# minimumSystem_1.net
KiCad netlist of a schematic drawn in EAGLE
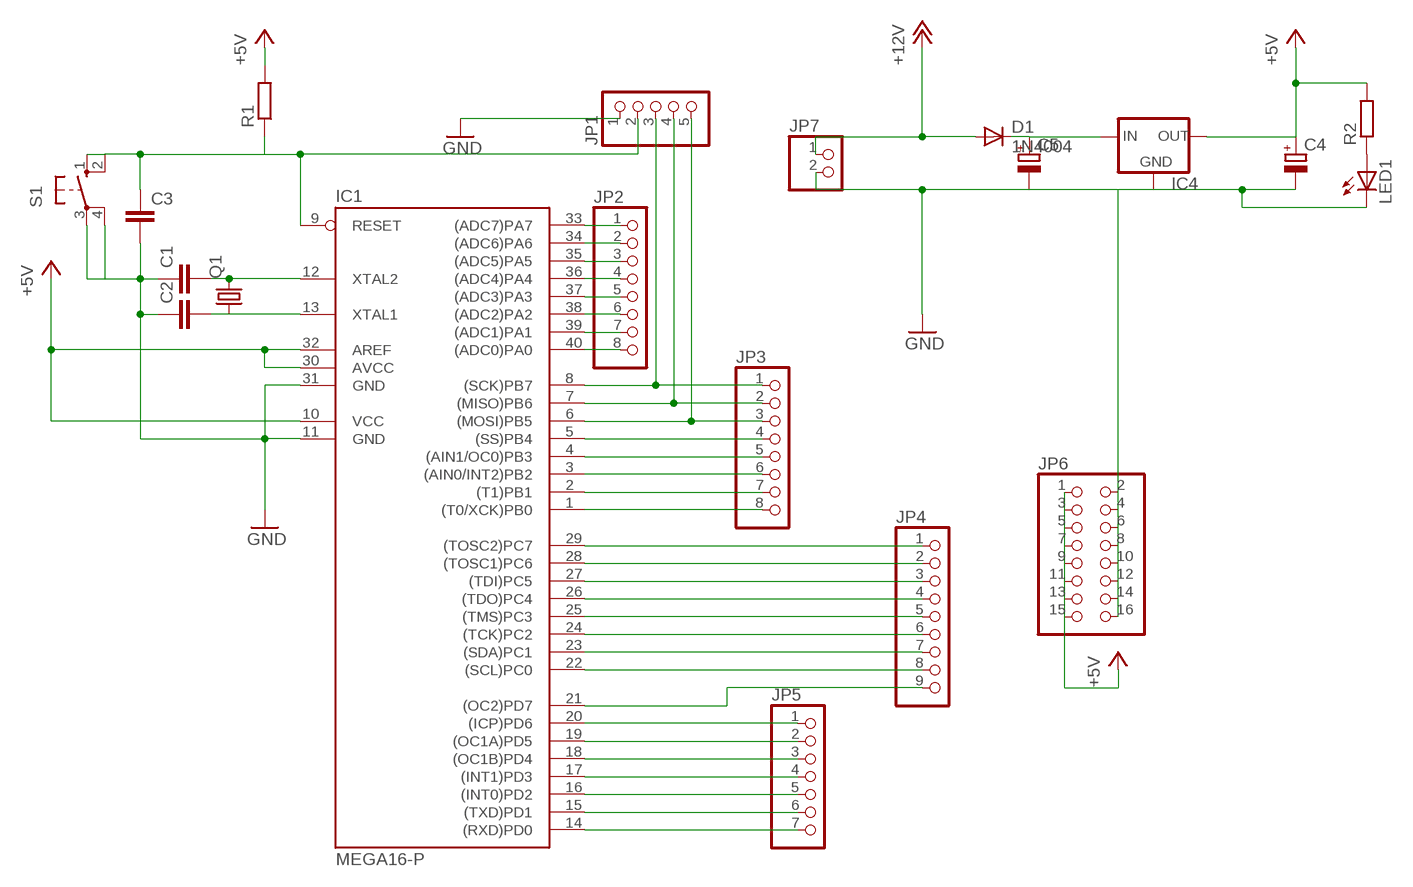
[diagram p0: schematic, sheet 1]

(export (version "E")
  (design (tool "Eeschema 10.0.6"))
  (components
    (comp (ref "C1")
      (value "C-EU025-024X044")
      (footprint "eagle-import:C025-024X044")
      (libsource (lib "eagle-import") (part "C-EU025-024X044"))
    )
    (comp (ref "C2")
      (value "C-EU025-024X044")
      (footprint "eagle-import:C025-024X044")
      (libsource (lib "eagle-import") (part "C-EU025-024X044"))
    )
    (comp (ref "C3")
      (value "C-EU050-025X075")
      (footprint "eagle-import:C050-025X075")
      (libsource (lib "eagle-import") (part "resistor_C-EU050-025X075"))
    )
    (comp (ref "C4")
      (value "CPOL-EUE2.5-5")
      (footprint "eagle-import:E2,5-5")
      (libsource (lib "eagle-import") (part "CPOL-EUE2.5-5"))
    )
    (comp (ref "C5")
      (value "CPOL-EUE2.5-5")
      (footprint "eagle-import:E2,5-5")
      (libsource (lib "eagle-import") (part "CPOL-EUE2.5-5"))
    )
    (comp (ref "D1")
      (value "1N4004")
      (footprint "eagle-import:DO41-10")
      (libsource (lib "eagle-import") (part "1N4004"))
    )
    (comp (ref "IC1")
      (value "MEGA16-P")
      (footprint "eagle-import:DIL40")
      (fields (field (name "MPN") "ATMEGA16-16PU"))
      (libsource (lib "eagle-import") (part "MEGA16-P"))
    )
    (comp (ref "IC4")
      (value "78XXS")
      (footprint "eagle-import:78XXS")
      (libsource (lib "eagle-import") (part "78XXS"))
    )
    (comp (ref "JP1")
      (value "PINHD-1X5")
      (footprint "eagle-import:1X05")
      (libsource (lib "eagle-import") (part "PINHD-1X5"))
    )
    (comp (ref "JP2")
      (value "PINHD-1X8")
      (footprint "eagle-import:1X08")
      (libsource (lib "eagle-import") (part "PINHD-1X8"))
    )
    (comp (ref "JP3")
      (value "PINHD-1X8")
      (footprint "eagle-import:1X08")
      (libsource (lib "eagle-import") (part "PINHD-1X8"))
    )
    (comp (ref "JP4")
      (value "PINHD-1X9")
      (footprint "eagle-import:1X09")
      (libsource (lib "eagle-import") (part "PINHD-1X9"))
    )
    (comp (ref "JP5")
      (value "PINHD-1X7")
      (footprint "eagle-import:1X07")
      (libsource (lib "eagle-import") (part "PINHD-1X7"))
    )
    (comp (ref "JP6")
      (value "PINHD-2X8")
      (footprint "eagle-import:2X08")
      (libsource (lib "eagle-import") (part "PINHD-2X8"))
    )
    (comp (ref "JP7")
      (value "PINHD-1X2")
      (footprint "eagle-import:1X02")
      (libsource (lib "eagle-import") (part "PINHD-1X2"))
    )
    (comp (ref "LED1")
      (value "LED5MM")
      (footprint "eagle-import:LED5MM")
      (libsource (lib "eagle-import") (part "LED5MM"))
    )
    (comp (ref "Q1")
      (value "CRYSTALHC49U-V")
      (footprint "eagle-import:HC49U-V")
      (libsource (lib "eagle-import") (part "CRYSTALHC49U-V"))
    )
    (comp (ref "R1")
      (value "R-EU_0204/7")
      (footprint "eagle-import:0204_7")
      (libsource (lib "eagle-import") (part "R-EU_0204/7"))
    )
    (comp (ref "R2")
      (value "R-EU_0204/7")
      (footprint "eagle-import:0204_7")
      (libsource (lib "eagle-import") (part "R-EU_0204/7"))
    )
    (comp (ref "S1")
      (value "10-XX")
      (footprint "eagle-import:B3F-10XX")
      (fields (field (name "MPN") "B3F-1000"))
      (libsource (lib "eagle-import") (part "10-XX"))
    )
  )
  (nets
    (net (code "1") (name "+5V") (class "Default")
      (node (ref "C4") (pin "+") (pinfunction "+_+") (pintype "passive"))
      (node (ref "IC1") (pin "10") (pinfunction "VCC_10") (pintype "power_in"))
      (node (ref "IC1") (pin "30") (pinfunction "AVCC_30") (pintype "power_in"))
      (node (ref "IC1") (pin "32") (pinfunction "AREF_32") (pintype "passive"))
      (node (ref "IC4") (pin "OUT") (pinfunction "OUT_OUT") (pintype "passive"))
      (node (ref "JP6") (pin "1") (pinfunction "1_1") (pintype "passive"))
      (node (ref "JP6") (pin "11") (pinfunction "11_11") (pintype "passive"))
      (node (ref "JP6") (pin "13") (pinfunction "13_13") (pintype "passive"))
      (node (ref "JP6") (pin "15") (pinfunction "15_15") (pintype "passive"))
      (node (ref "JP6") (pin "3") (pinfunction "3_3") (pintype "passive"))
      (node (ref "JP6") (pin "5") (pinfunction "5_5") (pintype "passive"))
      (node (ref "JP6") (pin "7") (pinfunction "7_7") (pintype "passive"))
      (node (ref "JP6") (pin "9") (pinfunction "9_9") (pintype "passive"))
      (node (ref "R1") (pin "2") (pinfunction "2_2") (pintype "passive"))
      (node (ref "R2") (pin "2") (pinfunction "2_2") (pintype "passive"))
    )
    (net (code "2") (name "+12V") (class "Default")
      (node (ref "D1") (pin "A") (pinfunction "A_A") (pintype "passive"))
      (node (ref "JP7") (pin "1") (pinfunction "1_1") (pintype "passive"))
    )
    (net (code "3") (name "GND") (class "Default")
      (node (ref "C1") (pin "1") (pinfunction "1_1") (pintype "passive"))
      (node (ref "C2") (pin "1") (pinfunction "1_1") (pintype "passive"))
      (node (ref "C3") (pin "2") (pinfunction "2_2") (pintype "passive"))
      (node (ref "C4") (pin "-") (pinfunction "-_-") (pintype "passive"))
      (node (ref "C5") (pin "-") (pinfunction "-_-") (pintype "passive"))
      (node (ref "IC1") (pin "11") (pinfunction "GND_11") (pintype "power_in"))
      (node (ref "IC1") (pin "31") (pinfunction "GND_31") (pintype "power_in"))
      (node (ref "IC4") (pin "GND") (pinfunction "GND_GND") (pintype "input"))
      (node (ref "JP1") (pin "1") (pinfunction "1_1") (pintype "passive"))
      (node (ref "JP6") (pin "10") (pinfunction "10_10") (pintype "passive"))
      (node (ref "JP6") (pin "12") (pinfunction "12_12") (pintype "passive"))
      (node (ref "JP6") (pin "14") (pinfunction "14_14") (pintype "passive"))
      (node (ref "JP6") (pin "16") (pinfunction "16_16") (pintype "passive"))
      (node (ref "JP6") (pin "2") (pinfunction "2_2") (pintype "passive"))
      (node (ref "JP6") (pin "4") (pinfunction "4_4") (pintype "passive"))
      (node (ref "JP6") (pin "6") (pinfunction "6_6") (pintype "passive"))
      (node (ref "JP6") (pin "8") (pinfunction "8_8") (pintype "passive"))
      (node (ref "JP7") (pin "2") (pinfunction "2_2") (pintype "passive"))
      (node (ref "LED1") (pin "K") (pinfunction "C_K") (pintype "passive"))
      (node (ref "S1") (pin "3") (pinfunction "P_3") (pintype "passive"))
      (node (ref "S1") (pin "4") (pinfunction "P1_4") (pintype "passive"))
    )
    (net (code "4") (name "Net-(C5-Pad+)") (class "Default")
      (node (ref "C5") (pin "+") (pinfunction "+_+") (pintype "passive"))
      (node (ref "D1") (pin "C") (pinfunction "C_C") (pintype "passive"))
      (node (ref "IC4") (pin "IN") (pinfunction "IN_IN") (pintype "input"))
    )
    (net (code "5") (name "Net-(IC1-(ADC0)PA0)") (class "Default")
      (node (ref "IC1") (pin "40") (pinfunction "(ADC0)PA0_40") (pintype "bidirectional"))
      (node (ref "JP2") (pin "8") (pinfunction "8_8") (pintype "passive"))
    )
    (net (code "6") (name "Net-(IC1-(ADC1)PA1)") (class "Default")
      (node (ref "IC1") (pin "39") (pinfunction "(ADC1)PA1_39") (pintype "bidirectional"))
      (node (ref "JP2") (pin "7") (pinfunction "7_7") (pintype "passive"))
    )
    (net (code "7") (name "Net-(IC1-(ADC2)PA2)") (class "Default")
      (node (ref "IC1") (pin "38") (pinfunction "(ADC2)PA2_38") (pintype "bidirectional"))
      (node (ref "JP2") (pin "6") (pinfunction "6_6") (pintype "passive"))
    )
    (net (code "8") (name "Net-(IC1-(ADC3)PA3)") (class "Default")
      (node (ref "IC1") (pin "37") (pinfunction "(ADC3)PA3_37") (pintype "bidirectional"))
      (node (ref "JP2") (pin "5") (pinfunction "5_5") (pintype "passive"))
    )
    (net (code "9") (name "Net-(IC1-(ADC4)PA4)") (class "Default")
      (node (ref "IC1") (pin "36") (pinfunction "(ADC4)PA4_36") (pintype "bidirectional"))
      (node (ref "JP2") (pin "4") (pinfunction "4_4") (pintype "passive"))
    )
    (net (code "10") (name "Net-(IC1-(ADC5)PA5)") (class "Default")
      (node (ref "IC1") (pin "35") (pinfunction "(ADC5)PA5_35") (pintype "bidirectional"))
      (node (ref "JP2") (pin "3") (pinfunction "3_3") (pintype "passive"))
    )
    (net (code "11") (name "Net-(IC1-(ADC6)PA6)") (class "Default")
      (node (ref "IC1") (pin "34") (pinfunction "(ADC6)PA6_34") (pintype "bidirectional"))
      (node (ref "JP2") (pin "2") (pinfunction "2_2") (pintype "passive"))
    )
    (net (code "12") (name "Net-(IC1-(ADC7)PA7)") (class "Default")
      (node (ref "IC1") (pin "33") (pinfunction "(ADC7)PA7_33") (pintype "bidirectional"))
      (node (ref "JP2") (pin "1") (pinfunction "1_1") (pintype "passive"))
    )
    (net (code "13") (name "Net-(IC1-(AIN0{slash}INT2)PB2)") (class "Default")
      (node (ref "IC1") (pin "3") (pinfunction "(AIN0/INT2)PB2_3") (pintype "bidirectional"))
      (node (ref "JP3") (pin "6") (pinfunction "6_6") (pintype "passive"))
    )
    (net (code "14") (name "Net-(IC1-(AIN1{slash}OC0)PB3)") (class "Default")
      (node (ref "IC1") (pin "4") (pinfunction "(AIN1/OC0)PB3_4") (pintype "bidirectional"))
      (node (ref "JP3") (pin "5") (pinfunction "5_5") (pintype "passive"))
    )
    (net (code "15") (name "Net-(IC1-(ICP)PD6)") (class "Default")
      (node (ref "IC1") (pin "20") (pinfunction "(ICP)PD6_20") (pintype "bidirectional"))
      (node (ref "JP5") (pin "1") (pinfunction "1_1") (pintype "passive"))
    )
    (net (code "16") (name "Net-(IC1-(INT0)PD2)") (class "Default")
      (node (ref "IC1") (pin "16") (pinfunction "(INT0)PD2_16") (pintype "bidirectional"))
      (node (ref "JP5") (pin "5") (pinfunction "5_5") (pintype "passive"))
    )
    (net (code "17") (name "Net-(IC1-(INT1)PD3)") (class "Default")
      (node (ref "IC1") (pin "17") (pinfunction "(INT1)PD3_17") (pintype "bidirectional"))
      (node (ref "JP5") (pin "4") (pinfunction "4_4") (pintype "passive"))
    )
    (net (code "18") (name "Net-(IC1-(MISO)PB6)") (class "Default")
      (node (ref "IC1") (pin "7") (pinfunction "(MISO)PB6_7") (pintype "bidirectional"))
      (node (ref "JP1") (pin "4") (pinfunction "4_4") (pintype "passive"))
      (node (ref "JP3") (pin "2") (pinfunction "2_2") (pintype "passive"))
    )
    (net (code "19") (name "Net-(IC1-(MOSI)PB5)") (class "Default")
      (node (ref "IC1") (pin "6") (pinfunction "(MOSI)PB5_6") (pintype "bidirectional"))
      (node (ref "JP1") (pin "5") (pinfunction "5_5") (pintype "passive"))
      (node (ref "JP3") (pin "3") (pinfunction "3_3") (pintype "passive"))
    )
    (net (code "20") (name "Net-(IC1-(OC1A)PD5)") (class "Default")
      (node (ref "IC1") (pin "19") (pinfunction "(OC1A)PD5_19") (pintype "bidirectional"))
      (node (ref "JP5") (pin "2") (pinfunction "2_2") (pintype "passive"))
    )
    (net (code "21") (name "Net-(IC1-(OC1B)PD4)") (class "Default")
      (node (ref "IC1") (pin "18") (pinfunction "(OC1B)PD4_18") (pintype "bidirectional"))
      (node (ref "JP5") (pin "3") (pinfunction "3_3") (pintype "passive"))
    )
    (net (code "22") (name "Net-(IC1-(OC2)PD7)") (class "Default")
      (node (ref "IC1") (pin "21") (pinfunction "(OC2)PD7_21") (pintype "bidirectional"))
      (node (ref "JP4") (pin "9") (pinfunction "9_9") (pintype "passive"))
    )
    (net (code "23") (name "Net-(IC1-(RXD)PD0)") (class "Default")
      (node (ref "IC1") (pin "14") (pinfunction "(RXD)PD0_14") (pintype "bidirectional"))
      (node (ref "JP5") (pin "7") (pinfunction "7_7") (pintype "passive"))
    )
    (net (code "24") (name "Net-(IC1-(SCK)PB7)") (class "Default")
      (node (ref "IC1") (pin "8") (pinfunction "(SCK)PB7_8") (pintype "bidirectional"))
      (node (ref "JP1") (pin "3") (pinfunction "3_3") (pintype "passive"))
      (node (ref "JP3") (pin "1") (pinfunction "1_1") (pintype "passive"))
    )
    (net (code "25") (name "Net-(IC1-(SCL)PC0)") (class "Default")
      (node (ref "IC1") (pin "22") (pinfunction "(SCL)PC0_22") (pintype "bidirectional"))
      (node (ref "JP4") (pin "8") (pinfunction "8_8") (pintype "passive"))
    )
    (net (code "26") (name "Net-(IC1-(SDA)PC1)") (class "Default")
      (node (ref "IC1") (pin "23") (pinfunction "(SDA)PC1_23") (pintype "bidirectional"))
      (node (ref "JP4") (pin "7") (pinfunction "7_7") (pintype "passive"))
    )
    (net (code "27") (name "Net-(IC1-(SS)PB4)") (class "Default")
      (node (ref "IC1") (pin "5") (pinfunction "(SS)PB4_5") (pintype "bidirectional"))
      (node (ref "JP3") (pin "4") (pinfunction "4_4") (pintype "passive"))
    )
    (net (code "28") (name "Net-(IC1-(T0{slash}XCK)PB0)") (class "Default")
      (node (ref "IC1") (pin "1") (pinfunction "(T0/XCK)PB0_1") (pintype "bidirectional"))
      (node (ref "JP3") (pin "8") (pinfunction "8_8") (pintype "passive"))
    )
    (net (code "29") (name "Net-(IC1-(T1)PB1)") (class "Default")
      (node (ref "IC1") (pin "2") (pinfunction "(T1)PB1_2") (pintype "bidirectional"))
      (node (ref "JP3") (pin "7") (pinfunction "7_7") (pintype "passive"))
    )
    (net (code "30") (name "Net-(IC1-(TCK)PC2)") (class "Default")
      (node (ref "IC1") (pin "24") (pinfunction "(TCK)PC2_24") (pintype "bidirectional"))
      (node (ref "JP4") (pin "6") (pinfunction "6_6") (pintype "passive"))
    )
    (net (code "31") (name "Net-(IC1-(TDI)PC5)") (class "Default")
      (node (ref "IC1") (pin "27") (pinfunction "(TDI)PC5_27") (pintype "bidirectional"))
      (node (ref "JP4") (pin "3") (pinfunction "3_3") (pintype "passive"))
    )
    (net (code "32") (name "Net-(IC1-(TDO)PC4)") (class "Default")
      (node (ref "IC1") (pin "26") (pinfunction "(TDO)PC4_26") (pintype "bidirectional"))
      (node (ref "JP4") (pin "4") (pinfunction "4_4") (pintype "passive"))
    )
    (net (code "33") (name "Net-(IC1-(TMS)PC3)") (class "Default")
      (node (ref "IC1") (pin "25") (pinfunction "(TMS)PC3_25") (pintype "bidirectional"))
      (node (ref "JP4") (pin "5") (pinfunction "5_5") (pintype "passive"))
    )
    (net (code "34") (name "Net-(IC1-(TOSC1)PC6)") (class "Default")
      (node (ref "IC1") (pin "28") (pinfunction "(TOSC1)PC6_28") (pintype "bidirectional"))
      (node (ref "JP4") (pin "2") (pinfunction "2_2") (pintype "passive"))
    )
    (net (code "35") (name "Net-(IC1-(TOSC2)PC7)") (class "Default")
      (node (ref "IC1") (pin "29") (pinfunction "(TOSC2)PC7_29") (pintype "bidirectional"))
      (node (ref "JP4") (pin "1") (pinfunction "1_1") (pintype "passive"))
    )
    (net (code "36") (name "Net-(IC1-(TXD)PD1)") (class "Default")
      (node (ref "IC1") (pin "15") (pinfunction "(TXD)PD1_15") (pintype "bidirectional"))
      (node (ref "JP5") (pin "6") (pinfunction "6_6") (pintype "passive"))
    )
    (net (code "37") (name "Net-(IC1-RESET)") (class "Default")
      (node (ref "C3") (pin "1") (pinfunction "1_1") (pintype "passive"))
      (node (ref "IC1") (pin "9") (pinfunction "RESET_9") (pintype "input"))
      (node (ref "JP1") (pin "2") (pinfunction "2_2") (pintype "passive"))
      (node (ref "S1") (pin "1") (pinfunction "S_1") (pintype "passive"))
      (node (ref "S1") (pin "2") (pinfunction "S1_2") (pintype "passive"))
    )
    (net (code "38") (name "Net-(IC1-XTAL1)") (class "Default")
      (node (ref "C2") (pin "2") (pinfunction "2_2") (pintype "passive"))
      (node (ref "IC1") (pin "13") (pinfunction "XTAL1_13") (pintype "bidirectional"))
      (node (ref "Q1") (pin "1") (pinfunction "1_1") (pintype "passive"))
    )
    (net (code "39") (name "Net-(IC1-XTAL2)") (class "Default")
      (node (ref "C1") (pin "2") (pinfunction "2_2") (pintype "passive"))
      (node (ref "IC1") (pin "12") (pinfunction "XTAL2_12") (pintype "bidirectional"))
      (node (ref "Q1") (pin "2") (pinfunction "2_2") (pintype "passive"))
    )
    (net (code "40") (name "Net-(LED1-PadA)") (class "Default")
      (node (ref "LED1") (pin "A") (pinfunction "A_A") (pintype "passive"))
      (node (ref "R2") (pin "1") (pinfunction "1_1") (pintype "passive"))
    )
    (net (code "41") (name "unconnected-(R1-Pad1)") (class "Default")
      (node (ref "R1") (pin "1") (pinfunction "1_1") (pintype "passive"))
    )
  )
)
